# booster.net
KiCad netlist of a schematic drawn in Altium Designer
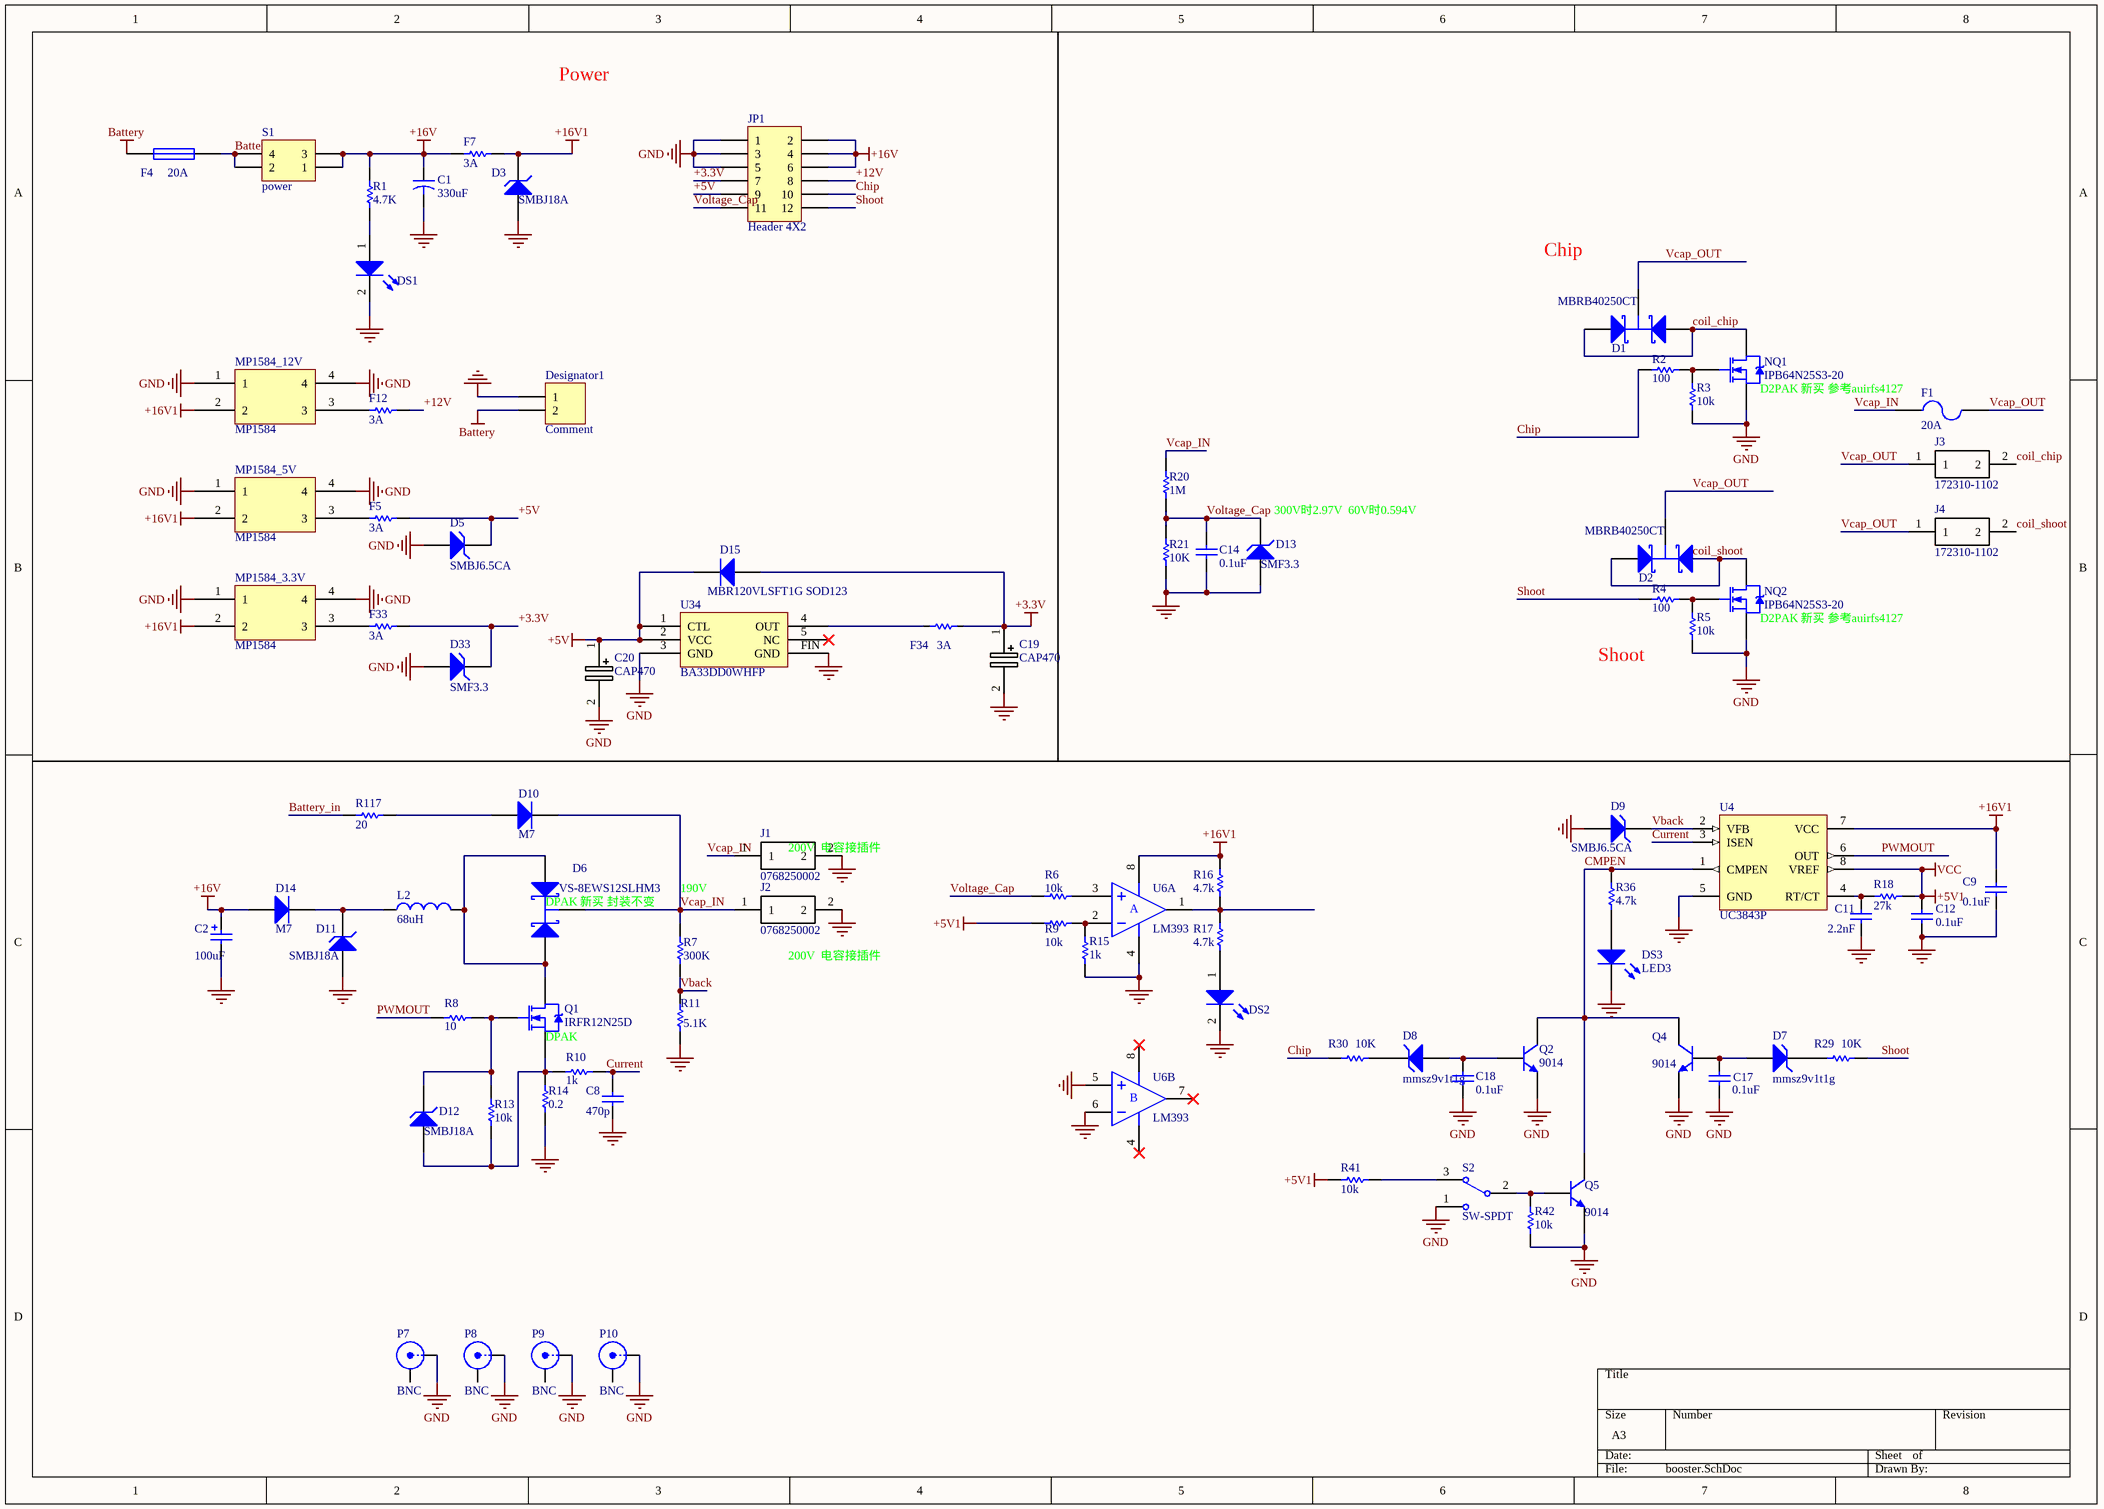
[diagram p0: booster.SchDoc]

(export (version "E")
  (design (tool "Eeschema 10.0.6"))
  (components
    (comp (ref "C1")
      (value "330uF")
      (footprint "470uF")
      (description "Capacitor")
      (fields (field (name "PUBLISHER") "Altium Limited"))
      (libsource (lib "Miscellaneous Devices") (part "Cap2"))
    )
    (comp (ref "C2")
      (value "100uF")
      (footprint "100uF")
      (description "Polarized Capacitor (Radial)")
      (fields
        (field (name "MANUFACTURER") "Generic Components")
        (field (name "Comment") "100uf")
        (field (name "PUBLISHER") "Altium Hobart Technology Centre")
      )
      (libsource (lib "Miscellaneous Devices") (part "Cap Pol1"))
    )
    (comp (ref "C8")
      (value "470p")
      (footprint "0805C")
      (description "Capacitor")
      (fields
        (field (name "MANUFACTURER") "Generic Components")
        (field (name "PUBLISHER") "Altium Hobart Technology Centre")
      )
      (libsource (lib "Miscellaneous Devices") (part "Cap"))
    )
    (comp (ref "C9")
      (value "0.1uF")
      (footprint "0805C")
      (description "Capacitor")
      (fields (field (name "PUBLISHER") "Altium Limited"))
      (libsource (lib "Miscellaneous Devices") (part "Cap"))
    )
    (comp (ref "C11")
      (value "2.2nF")
      (footprint "0805C")
      (description "Capacitor")
      (fields
        (field (name "MANUFACTURER") "Generic Components")
        (field (name "Comment") "2.2nf")
        (field (name "PUBLISHER") "Altium Hobart Technology Centre")
      )
      (libsource (lib "Miscellaneous Devices") (part "Cap"))
    )
    (comp (ref "C12")
      (value "0.1uF")
      (footprint "0805C")
      (description "Capacitor")
      (fields
        (field (name "MANUFACTURER") "Generic Components")
        (field (name "PUBLISHER") "Altium Hobart Technology Centre")
      )
      (libsource (lib "Miscellaneous Devices") (part "Cap"))
    )
    (comp (ref "C14")
      (value "0.1uF")
      (footprint "0805C")
      (description "Capacitor")
      (fields (field (name "PUBLISHER") "Altium Limited"))
      (libsource (lib "Miscellaneous Devices") (part "Cap"))
    )
    (comp (ref "C17")
      (value "0.1uF")
      (footprint "0805c")
      (description "Capacitor")
      (fields (field (name "PUBLISHER") "Altium Limited"))
      (libsource (lib "Miscellaneous Devices") (part "Cap"))
    )
    (comp (ref "C18")
      (value "0.1uF")
      (footprint "0805c")
      (description "Capacitor")
      (fields (field (name "PUBLISHER") "Altium Limited"))
      (libsource (lib "Miscellaneous Devices") (part "Cap"))
    )
    (comp (ref "C19")
      (value "CAP470")
      (footprint "Main_Board:CAPPM7360X200N")
      (description "470uF电容贴片")
      (fields
        (field (name "MANUFACTURER_PART_NUMBER") "T523H477M016APE0707280")
        (field (name "MOUSER PART NUMBER") "80-T523H477M16P070LR")
      )
      (libsource (lib "Main_Board") (part "T523H477M016APE0707280"))
    )
    (comp (ref "C20")
      (value "CAP470")
      (footprint "Main_Board:CAPPM7360X200N")
      (description "470uF电容贴片")
      (fields
        (field (name "MANUFACTURER_PART_NUMBER") "T523H477M016APE0707280")
        (field (name "MOUSER PART NUMBER") "80-T523H477M16P070LR")
      )
      (libsource (lib "Main_Board") (part "T523H477M016APE0707280"))
    )
    (comp (ref "D1")
      (value "MBRB40250CT")
      (footprint "D2PAK")
      (description "Schottky Rectifier")
      (fields
        (field (name "MANUFACTURER") "International Rectifier")
        (field (name "PUBLISHER") "Altium Hobart Technology Centre")
      )
      (libsource (lib "IR Discrete Diode") (part "MBRB1545CT"))
    )
    (comp (ref "D2")
      (value "MBRB40250CT")
      (footprint "D2PAK")
      (description "Schottky Rectifier")
      (fields
        (field (name "MANUFACTURER") "International Rectifier")
        (field (name "PUBLISHER") "Altium Hobart Technology Centre")
      )
      (libsource (lib "IR Discrete Diode") (part "MBRB1545CT"))
    )
    (comp (ref "D3")
      (value "SMBJ18A")
      (footprint "booster:SMBJ6.5")
      (description "Zener Diode")
      (fields (field (name "PUBLISHER") "Altium Limited"))
      (libsource (lib "Miscellaneous Devices") (part "D Zener"))
    )
    (comp (ref "D5")
      (value "SMBJ6.5CA")
      (footprint "SMBJ6.5")
      (description "Zener Diode")
      (fields (field (name "PUBLISHER") "Altium Limited"))
      (libsource (lib "Miscellaneous Devices") (part "D Zener"))
    )
    (comp (ref "D6")
      (value "VS-8EWS12SLHM3")
      (footprint "DPAK")
      (description "Schottky Rectifier")
      (fields
        (field (name "MANUFACTURER") "International Rectifier")
        (field (name "PUBLISHER") "Altium Hobart Technology Centre")
      )
      (libsource (lib "IR Discrete Diode") (part "MBRB1545CT"))
    )
    (comp (ref "D7")
      (value "mmsz9v1t1g")
      (footprint "sod-123")
      (description "Zener Diode")
      (fields (field (name "PUBLISHER") "Altium Limited"))
      (libsource (lib "Miscellaneous Devices") (part "D Zener"))
    )
    (comp (ref "D8")
      (value "mmsz9v1t1g")
      (footprint "sod-123")
      (description "Zener Diode")
      (fields (field (name "PUBLISHER") "Altium Limited"))
      (libsource (lib "Miscellaneous Devices") (part "D Zener"))
    )
    (comp (ref "D9")
      (value "SMBJ6.5CA")
      (footprint "SMBJ6.5")
      (description "Zener Diode")
      (fields (field (name "PUBLISHER") "Altium Limited"))
      (libsource (lib "Miscellaneous Devices") (part "D Zener"))
    )
    (comp (ref "D10")
      (value "M7")
      (footprint "booster:SMA")
      (description "Default Diode")
      (fields
        (field (name "MANUFACTURER") "Generic Components")
        (field (name "PUBLISHER") "Altium Hobart Technology Centre")
      )
      (libsource (lib "Miscellaneous Devices") (part "Diode"))
    )
    (comp (ref "D11")
      (value "SMBJ18A")
      (footprint "booster:SMBJ6.5")
      (description "Zener Diode")
      (fields (field (name "PUBLISHER") "Altium Limited"))
      (libsource (lib "Miscellaneous Devices") (part "D Zener"))
    )
    (comp (ref "D12")
      (value "SMBJ18A")
      (footprint "SMBJ6.5")
      (description "Zener Diode")
      (fields (field (name "PUBLISHER") "Altium Limited"))
      (libsource (lib "Miscellaneous Devices") (part "D Zener"))
    )
    (comp (ref "D13")
      (value "SMF3.3")
      (footprint "SMF33")
      (description "Zener Diode")
      (fields (field (name "PUBLISHER") "Altium Limited"))
      (libsource (lib "Miscellaneous Devices") (part "D Zener"))
    )
    (comp (ref "D14")
      (value "M7")
      (footprint "booster:SMA")
      (description "Default Diode")
      (fields
        (field (name "MANUFACTURER") "Generic Components")
        (field (name "PUBLISHER") "Altium Hobart Technology Centre")
      )
      (libsource (lib "Miscellaneous Devices") (part "Diode"))
    )
    (comp (ref "D15")
      (value "MBR120VLSFT1G SOD123")
      (footprint "Main_Board:sod123")
      (description "Default Diode")
      (fields
        (field (name "MANUFACTURER") "Generic Components")
        (field (name "PUBLISHER") "Altium Hobart Technology Centre")
      )
      (libsource (lib "Miscellaneous Devices") (part "Diode"))
    )
    (comp (ref "D33")
      (value "SMF3.3")
      (footprint "SMF33")
      (description "Zener Diode")
      (fields (field (name "PUBLISHER") "Altium Limited"))
      (libsource (lib "Miscellaneous Devices") (part "D Zener"))
    )
    (comp (ref "Designator1")
      (value "Comment")
      (footprint "XT60PW")
      (description "Header, 2-Pin")
      (fields (field (name "PUBLISHER") "Altium Limited"))
      (libsource (lib "Miscellaneous Connectors") (part "Header 2"))
    )
    (comp (ref "DS1")
      (value "LED2")
      (footprint "0805A")
      (description "Typical RED, GREEN, YELLOW, AMBER GaAs LED")
      (fields
        (field (name "MANUFACTURER") "Generic Components")
        (field (name "PUBLISHER") "Altium Hobart Technology Centre")
      )
      (libsource (lib "Miscellaneous Devices") (part "LED2"))
    )
    (comp (ref "DS2")
      (value "LED2")
      (footprint "0805A")
      (description "Typical RED, GREEN, YELLOW, AMBER GaAs LED")
      (fields
        (field (name "MANUFACTURER") "Generic Components")
        (field (name "PUBLISHER") "Altium Hobart Technology Centre")
      )
      (libsource (lib "Miscellaneous Devices") (part "LED2"))
    )
    (comp (ref "DS3")
      (value "LED3")
      (footprint "booster:0805A")
      (description "Typical RED, GREEN, YELLOW, AMBER GaAs LED")
      (fields (field (name "PUBLISHER") "Altium Limited"))
      (libsource (lib "") (part "LED2_1"))
    )
    (comp (ref "F1")
      (value "20A")
      (footprint "20A")
      (fields (field (name "PUBLISHER") "Altium Limited"))
      (libsource (lib "Miscellaneous Devices") (part "Fuse 2"))
    )
    (comp (ref "F4")
      (value "20A")
      (footprint "20A")
      (description "Fuse")
      (fields (field (name "PUBLISHER") "Altium Limited"))
      (libsource (lib "Miscellaneous Devices") (part "Fuse 1"))
    )
    (comp (ref "F5")
      (value "3A")
      (footprint "2512r")
      (description "Resistor")
      (fields
        (field (name "MANUFACTURER") "Generic Components")
        (field (name "PUBLISHER") "Altium Hobart Technology Centre")
      )
      (libsource (lib "Miscellaneous Devices") (part "Res1"))
    )
    (comp (ref "F7")
      (value "3A")
      (footprint "2512r")
      (description "Resistor")
      (fields
        (field (name "MANUFACTURER") "Generic Components")
        (field (name "PUBLISHER") "Altium Hobart Technology Centre")
      )
      (libsource (lib "Miscellaneous Devices") (part "Res1"))
    )
    (comp (ref "F12")
      (value "3A")
      (footprint "2512r")
      (description "Resistor")
      (fields
        (field (name "MANUFACTURER") "Generic Components")
        (field (name "PUBLISHER") "Altium Hobart Technology Centre")
      )
      (libsource (lib "Miscellaneous Devices") (part "Res1"))
    )
    (comp (ref "F33")
      (value "3A")
      (footprint "2512r")
      (description "Resistor")
      (fields
        (field (name "MANUFACTURER") "Generic Components")
        (field (name "PUBLISHER") "Altium Hobart Technology Centre")
      )
      (libsource (lib "Miscellaneous Devices") (part "Res1"))
    )
    (comp (ref "F34")
      (value "3A")
      (footprint "2512r")
      (description "Resistor")
      (fields (field (name "PUBLISHER") "Altium Limited"))
      (libsource (lib "") (part "Res1_1"))
    )
    (comp (ref "J1")
      (value "0768250002")
      (footprint "booster:0768250002_version2")
      (description "Connector")
      (libsource (lib "booster") (part "0768250002"))
    )
    (comp (ref "J2")
      (value "0768250002")
      (footprint "booster:0768250002_version2")
      (description "Connector")
      (libsource (lib "booster") (part "0768250002"))
    )
    (comp (ref "J3")
      (value "172310-1102")
      (footprint "booster:172310-1102_VERSION2")
      (description "Connector")
      (fields (field (name "MOUSER PART NUMBER") "538-172310-1102") (field (name "RS PART NUMBER") "8951880"))
      (libsource (lib "booster") (part "172310-1102"))
    )
    (comp (ref "J4")
      (value "172310-1102")
      (footprint "booster:172310-1102_VERSION2")
      (description "Connector")
      (fields (field (name "MOUSER PART NUMBER") "538-172310-1102") (field (name "RS PART NUMBER") "8951880"))
      (libsource (lib "booster") (part "172310-1102"))
    )
    (comp (ref "JP1")
      (value "Header 4X2")
      (footprint "2*6_2.5mm")
      (description "Header, 4-Pin, Dual row")
      (fields (field (name "PUBLISHER") "Altium Limited"))
      (libsource (lib "booster") (part "Header 6X2"))
    )
    (comp (ref "L2")
      (value "68uH")
      (footprint "INDPM120120X1020N")
      (description "Inductor")
      (fields (field (name "PUBLISHER") "Altium Limited"))
      (libsource (lib "Miscellaneous Devices") (part "Inductor"))
    )
    (comp (ref "MP1584_3.3V") (value "MP1584") (footprint "1584") (libsource (lib "booster") (part "MP1584")))
    (comp (ref "MP1584_5V") (value "MP1584") (footprint "1584") (libsource (lib "booster") (part "MP1584")))
    (comp (ref "MP1584_12V") (value "MP1584") (footprint "1584") (libsource (lib "booster") (part "MP1584")))
    (comp (ref "NQ1")
      (value "IPB64N25S3-20")
      (footprint "D2PAK")
      (description "HEXFET Power MOSFET")
      (fields
        (field (name "MANUFACTURER") "International Rectifier")
        (field (name "PUBLISHER") "Altium Hobart Technology Centre")
      )
      (libsource (lib "IR Discrete MOSFET") (part "IRFP460"))
    )
    (comp (ref "NQ2")
      (value "IPB64N25S3-20")
      (footprint "D2PAK")
      (description "HEXFET Power MOSFET")
      (fields
        (field (name "MANUFACTURER") "International Rectifier")
        (field (name "PUBLISHER") "Altium Hobart Technology Centre")
      )
      (libsource (lib "IR Discrete MOSFET") (part "IRFP460"))
    )
    (comp (ref "P7")
      (value "BNC")
      (footprint "hole")
      (description "BNC Elbow Connector")
      (fields (field (name "PUBLISHER") "Altium Limited"))
      (libsource (lib "Miscellaneous Connectors") (part "BNC"))
    )
    (comp (ref "P8")
      (value "BNC")
      (footprint "hole")
      (description "BNC Elbow Connector")
      (fields (field (name "PUBLISHER") "Altium Limited"))
      (libsource (lib "Miscellaneous Connectors") (part "BNC"))
    )
    (comp (ref "P9")
      (value "BNC")
      (footprint "hole")
      (description "BNC Elbow Connector")
      (fields (field (name "PUBLISHER") "Altium Limited"))
      (libsource (lib "Miscellaneous Connectors") (part "BNC"))
    )
    (comp (ref "P10")
      (value "BNC")
      (footprint "hole")
      (description "BNC Elbow Connector")
      (fields (field (name "PUBLISHER") "Altium Limited"))
      (libsource (lib "Miscellaneous Connectors") (part "BNC"))
    )
    (comp (ref "Q1")
      (value "IRFR12N25D")
      (footprint "DPAK")
      (description "N-Channel Power MOSFET")
      (fields (field (name "PUBLISHER") "Altium Limited"))
      (libsource (lib "Miscellaneous Devices") (part "NMOS-2"))
    )
    (comp (ref "Q2")
      (value "9014")
      (footprint "元器件:SOT23A")
      (description "NPN General Purpose Amplifier")
      (fields
        (field (name "MANUFACTURER") "Fairchild Semiconductor")
        (field (name "PUBLISHER") "Altium Hobart Technology Centre")
      )
      (libsource (lib "FSC Discrete BJT") (part "BC817-40"))
    )
    (comp (ref "Q4")
      (value "9014")
      (footprint "sot23a")
      (description "NPN General Purpose Amplifier")
      (fields
        (field (name "MANUFACTURER") "Fairchild Semiconductor")
        (field (name "PUBLISHER") "Altium Hobart Technology Centre")
      )
      (libsource (lib "FSC Discrete BJT") (part "BC817-40"))
    )
    (comp (ref "Q5")
      (value "9014")
      (footprint "SOT23a")
      (description "NPN General Purpose Amplifier")
      (fields
        (field (name "MANUFACTURER") "Fairchild Semiconductor")
        (field (name "PUBLISHER") "Altium Hobart Technology Centre")
      )
      (libsource (lib "FSC Discrete BJT") (part "BC817-40"))
    )
    (comp (ref "R1")
      (value "4.7K")
      (footprint "0805R")
      (description "Resistor")
      (fields
        (field (name "MANUFACTURER") "Generic Components")
        (field (name "Comment") "4.7k")
        (field (name "PUBLISHER") "Altium Hobart Technology Centre")
      )
      (libsource (lib "Miscellaneous Devices") (part "Res1"))
    )
    (comp (ref "R2")
      (value "100")
      (footprint "0805r")
      (description "Semiconductor Resistor")
      (fields
        (field (name "MANUFACTURER") "Generic Components")
        (field (name "PUBLISHER") "Altium Hobart Technology Centre")
      )
      (libsource (lib "Miscellaneous Devices") (part "Res Semi"))
    )
    (comp (ref "R3")
      (value "10k")
      (footprint "0805R")
      (description "Semiconductor Resistor")
      (fields
        (field (name "MANUFACTURER") "Generic Components")
        (field (name "PUBLISHER") "Altium Hobart Technology Centre")
      )
      (libsource (lib "Miscellaneous Devices") (part "Res Semi"))
    )
    (comp (ref "R4")
      (value "100")
      (footprint "0805r")
      (description "Semiconductor Resistor")
      (fields
        (field (name "MANUFACTURER") "Generic Components")
        (field (name "PUBLISHER") "Altium Hobart Technology Centre")
      )
      (libsource (lib "Miscellaneous Devices") (part "Res Semi"))
    )
    (comp (ref "R5")
      (value "10k")
      (footprint "0805R")
      (description "Semiconductor Resistor")
      (fields
        (field (name "MANUFACTURER") "Generic Components")
        (field (name "PUBLISHER") "Altium Hobart Technology Centre")
      )
      (libsource (lib "Miscellaneous Devices") (part "Res Semi"))
    )
    (comp (ref "R6")
      (value "10k")
      (footprint "0805R")
      (description "Resistor")
      (fields
        (field (name "MANUFACTURER") "Generic Components")
        (field (name "PUBLISHER") "Altium Hobart Technology Centre")
      )
      (libsource (lib "HAIBAO_MEGAV1.0_1") (part "Res1"))
    )
    (comp (ref "R7")
      (value "300K")
      (footprint "0805R")
      (description "Resistor")
      (fields
        (field (name "MANUFACTURER") "Generic Components")
        (field (name "Comment") "390K")
        (field (name "PUBLISHER") "Altium Hobart Technology Centre")
      )
      (libsource (lib "Miscellaneous Devices") (part "Res1"))
    )
    (comp (ref "R8")
      (value "10")
      (footprint "0805R")
      (description "Resistor")
      (fields
        (field (name "MANUFACTURER") "Generic Components")
        (field (name "PUBLISHER") "Altium Hobart Technology Centre")
      )
      (libsource (lib "Miscellaneous Devices") (part "Res1"))
    )
    (comp (ref "R9")
      (value "10k")
      (footprint "0805R")
      (description "Resistor")
      (fields
        (field (name "MANUFACTURER") "Generic Components")
        (field (name "PUBLISHER") "Altium Hobart Technology Centre")
      )
      (libsource (lib "HAIBAO_MEGAV1.0_1") (part "Res1"))
    )
    (comp (ref "R10")
      (value "1k")
      (footprint "0805R")
      (description "Resistor")
      (fields
        (field (name "MANUFACTURER") "Generic Components")
        (field (name "PUBLISHER") "Altium Hobart Technology Centre")
      )
      (libsource (lib "Miscellaneous Devices") (part "Res1"))
    )
    (comp (ref "R11")
      (value "5.1K")
      (footprint "0805R")
      (description "Resistor")
      (fields
        (field (name "MANUFACTURER") "Generic Components")
        (field (name "Comment") "3.3K")
        (field (name "PUBLISHER") "Altium Hobart Technology Centre")
      )
      (libsource (lib "Miscellaneous Devices") (part "Res1"))
    )
    (comp (ref "R13")
      (value "10k")
      (footprint "0805R")
      (description "Resistor")
      (fields
        (field (name "MANUFACTURER") "Generic Components")
        (field (name "PUBLISHER") "Altium Hobart Technology Centre")
      )
      (libsource (lib "Miscellaneous Devices") (part "Res1"))
    )
    (comp (ref "R14")
      (value "0.2")
      (footprint "0.2_4527R")
      (description "Resistor")
      (fields
        (field (name "MANUFACTURER") "Generic Components")
        (field (name "PUBLISHER") "Altium Hobart Technology Centre")
      )
      (libsource (lib "Miscellaneous Devices") (part "Res1"))
    )
    (comp (ref "R15")
      (value "1k")
      (footprint "0805R")
      (description "Resistor")
      (fields
        (field (name "MANUFACTURER") "Generic Components")
        (field (name "PUBLISHER") "Altium Hobart Technology Centre")
      )
      (libsource (lib "HAIBAO_MEGAV1.0_1") (part "Res1"))
    )
    (comp (ref "R16")
      (value "4.7k")
      (footprint "0805R")
      (description "Resistor")
      (fields
        (field (name "MANUFACTURER") "Generic Components")
        (field (name "PUBLISHER") "Altium Hobart Technology Centre")
      )
      (libsource (lib "HAIBAO_MEGAV1.0_1") (part "Res1"))
    )
    (comp (ref "R17")
      (value "4.7k")
      (footprint "0805R")
      (description "Resistor")
      (fields
        (field (name "MANUFACTURER") "Generic Components")
        (field (name "PUBLISHER") "Altium Hobart Technology Centre")
      )
      (libsource (lib "HAIBAO_MEGAV1.0_1") (part "Res1"))
    )
    (comp (ref "R18")
      (value "27k")
      (footprint "0805R")
      (description "Resistor")
      (fields
        (field (name "MANUFACTURER") "Generic Components")
        (field (name "PUBLISHER") "Altium Hobart Technology Centre")
      )
      (libsource (lib "Miscellaneous Devices") (part "Res1"))
    )
    (comp (ref "R20")
      (value "1M")
      (footprint "0805R")
      (description "Resistor")
      (fields
        (field (name "MANUFACTURER") "Generic Components")
        (field (name "Comment") "200k")
        (field (name "PUBLISHER") "Altium Hobart Technology Centre")
      )
      (libsource (lib "Miscellaneous Devices") (part "Res1"))
    )
    (comp (ref "R21")
      (value "10K")
      (footprint "0805R")
      (description "Resistor")
      (fields
        (field (name "MANUFACTURER") "Generic Components")
        (field (name "Comment") "3.9k")
        (field (name "PUBLISHER") "Altium Hobart Technology Centre")
      )
      (libsource (lib "Miscellaneous Devices") (part "Res1"))
    )
    (comp (ref "R29")
      (value "10K")
      (footprint "0805r")
      (description "Resistor")
      (fields
        (field (name "MANUFACTURER") "Generic Components")
        (field (name "Comment") "10k")
        (field (name "PUBLISHER") "Altium Hobart Technology Centre")
      )
      (libsource (lib "Miscellaneous Devices") (part "Res1"))
    )
    (comp (ref "R30")
      (value "10K")
      (footprint "0805r")
      (description "Resistor")
      (fields
        (field (name "MANUFACTURER") "Generic Components")
        (field (name "Comment") "10k")
        (field (name "PUBLISHER") "Altium Hobart Technology Centre")
      )
      (libsource (lib "Miscellaneous Devices") (part "Res1"))
    )
    (comp (ref "R36")
      (value "4.7k")
      (footprint "0805r")
      (description "Resistor")
      (fields
        (field (name "MANUFACTURER") "Generic Components")
        (field (name "PUBLISHER") "Altium Hobart Technology Centre")
      )
      (libsource (lib "Miscellaneous Devices") (part "Res1"))
    )
    (comp (ref "R41")
      (value "10k")
      (footprint "0805r")
      (description "Resistor")
      (fields
        (field (name "MANUFACTURER") "Generic Components")
        (field (name "PUBLISHER") "Altium Hobart Technology Centre")
      )
      (libsource (lib "Miscellaneous Devices") (part "Res1"))
    )
    (comp (ref "R42")
      (value "10k")
      (footprint "0805r")
      (description "Resistor")
      (fields
        (field (name "MANUFACTURER") "Generic Components")
        (field (name "PUBLISHER") "Altium Hobart Technology Centre")
      )
      (libsource (lib "Miscellaneous Devices") (part "Res1"))
    )
    (comp (ref "R117")
      (value "20")
      (footprint "20_2512r")
      (description "Resistor")
      (fields
        (field (name "MANUFACTURER") "Generic Components")
        (field (name "PUBLISHER") "Altium Hobart Technology Centre")
      )
      (libsource (lib "Miscellaneous Devices") (part "Res1"))
    )
    (comp (ref "S1")
      (value "power")
      (footprint "Rocker_Switch")
      (description "Header, 2-Pin, Dual row")
      (fields (field (name "PUBLISHER") "Altium Limited"))
      (libsource (lib "Miscellaneous Connectors") (part "Header 2X2"))
    )
    (comp (ref "S2")
      (value "SW-SPDT")
      (footprint "SMALL_switch")
      (description "SPDT Subminiature Toggle Switch, Right Angle Mounting, Vertical Actuation")
      (fields (field (name "PUBLISHER") "Altium Limited"))
      (libsource (lib "Miscellaneous Devices") (part "SW-SPDT"))
    )
    (comp (ref "U4")
      (value "UC3843P")
      (footprint "SO-G8")
      (description "Current-Mode PWM Controller")
      (fields (field (name "PUBLISHER") "Altium Limited"))
      (libsource (lib "TI Power Mgt DC-DC Converter") (part "UC3843P"))
    )
    (comp (ref "U6")
      (value "LM393")
      (footprint "LM393_SO-G8")
      (libsource (lib "HAIBAO_MEGAV1.0_1") (part "LM393"))
    )
    (comp (ref "U34")
      (value "BA33DD0WHFP")
      (footprint "Main_Board:HRP5_16TO5")
      (libsource (lib "Main_Board") (part "HRP5-16TO5"))
    )
  )
  (nets
    (net (code "1") (name "+3.3V") (class "Default")
      (node (ref "C19") (pin "1") (pinfunction "+_1") (pintype "passive"))
      (node (ref "D15") (pin "1") (pinfunction "A_1") (pintype "passive"))
      (node (ref "D33") (pin "2") (pinfunction "K_2") (pintype "passive"))
      (node (ref "F33") (pin "1") (pinfunction "1_1") (pintype "passive"))
      (node (ref "F34") (pin "2") (pinfunction "2_2") (pintype "passive"))
      (node (ref "JP1") (pin "7") (pinfunction "7_7") (pintype "passive"))
    )
    (net (code "2") (name "+5V") (class "Default")
      (node (ref "C20") (pin "1") (pinfunction "+_1") (pintype "passive"))
      (node (ref "D15") (pin "2") (pinfunction "K_2") (pintype "passive"))
      (node (ref "D5") (pin "2") (pinfunction "K_2") (pintype "passive"))
      (node (ref "F5") (pin "1") (pinfunction "1_1") (pintype "passive"))
      (node (ref "JP1") (pin "9") (pinfunction "9_9") (pintype "passive"))
      (node (ref "U34") (pin "1") (pinfunction "CTL_1") (pintype "passive"))
      (node (ref "U34") (pin "2") (pinfunction "VCC_2") (pintype "passive"))
    )
    (net (code "3") (name "+5V1") (class "Default")
      (node (ref "C12") (pin "1") (pinfunction "1_1") (pintype "passive"))
      (node (ref "R18") (pin "2") (pinfunction "2_2") (pintype "passive"))
      (node (ref "R41") (pin "2") (pinfunction "2_2") (pintype "passive"))
      (node (ref "R9") (pin "2") (pinfunction "2_2") (pintype "passive"))
      (node (ref "U4") (pin "8") (pinfunction "VREF_8") (pintype "output"))
    )
    (net (code "4") (name "+16V") (class "Default")
      (node (ref "C1") (pin "1") (pinfunction "1_1") (pintype "passive"))
      (node (ref "C2") (pin "1") (pinfunction "1_1") (pintype "passive"))
      (node (ref "D14") (pin "1") (pinfunction "A_1") (pintype "passive"))
      (node (ref "F7") (pin "2") (pinfunction "2_2") (pintype "passive"))
      (node (ref "JP1") (pin "2") (pinfunction "2_2") (pintype "passive"))
      (node (ref "JP1") (pin "4") (pinfunction "4_4") (pintype "passive"))
      (node (ref "JP1") (pin "6") (pinfunction "6_6") (pintype "passive"))
      (node (ref "R1") (pin "2") (pinfunction "2_2") (pintype "passive"))
      (node (ref "S1") (pin "1") (pinfunction "1_1") (pintype "passive"))
      (node (ref "S1") (pin "3") (pinfunction "3_3") (pintype "passive"))
    )
    (net (code "5") (name "+16V1") (class "Default")
      (node (ref "C9") (pin "2") (pinfunction "2_2") (pintype "passive"))
      (node (ref "D3") (pin "2") (pinfunction "K_2") (pintype "passive"))
      (node (ref "F7") (pin "1") (pinfunction "1_1") (pintype "passive"))
      (node (ref "MP1584_12V") (pin "2") (pinfunction "2_2") (pintype "passive"))
      (node (ref "MP1584_3.3V") (pin "2") (pinfunction "2_2") (pintype "passive"))
      (node (ref "MP1584_5V") (pin "2") (pinfunction "2_2") (pintype "passive"))
      (node (ref "R16") (pin "2") (pinfunction "2_2") (pintype "passive"))
      (node (ref "U4") (pin "7") (pinfunction "VCC_7") (pintype "power_in"))
      (node (ref "U6") (pin "8") (pinfunction "V+_8") (pintype "power_in"))
    )
    (net (code "6") (name "/+12V") (class "Default")
      (node (ref "F12") (pin "1") (pinfunction "1_1") (pintype "passive"))
      (node (ref "JP1") (pin "8") (pinfunction "8_8") (pintype "passive"))
    )
    (net (code "7") (name "/Battery_in") (class "Default")
      (node (ref "F4") (pin "1") (pinfunction "1_1") (pintype "passive"))
      (node (ref "R117") (pin "2") (pinfunction "2_2") (pintype "passive"))
      (node (ref "S1") (pin "2") (pinfunction "2_2") (pintype "passive"))
      (node (ref "S1") (pin "4") (pinfunction "4_4") (pintype "passive"))
    )
    (net (code "8") (name "/CMPEN") (class "Default")
      (node (ref "Q2") (pin "3") (pinfunction "C_3") (pintype "passive"))
      (node (ref "Q4") (pin "3") (pinfunction "C_3") (pintype "passive"))
      (node (ref "Q5") (pin "3") (pinfunction "C_3") (pintype "passive"))
      (node (ref "R36") (pin "2") (pinfunction "2_2") (pintype "passive"))
      (node (ref "U4") (pin "1") (pinfunction "CMPEN_1") (pintype "output"))
    )
    (net (code "9") (name "/Chip") (class "Default")
      (node (ref "JP1") (pin "10") (pinfunction "10_10") (pintype "passive"))
      (node (ref "R2") (pin "1") (pinfunction "1_1") (pintype "passive"))
      (node (ref "R30") (pin "1") (pinfunction "1_1") (pintype "passive"))
    )
    (net (code "10") (name "/Current") (class "Default")
      (node (ref "C8") (pin "1") (pinfunction "1_1") (pintype "passive"))
      (node (ref "R10") (pin "2") (pinfunction "2_2") (pintype "passive"))
      (node (ref "U4") (pin "3") (pinfunction "ISEN_3") (pintype "input"))
    )
    (net (code "11") (name "/PWMOUT") (class "Default")
      (node (ref "R8") (pin "1") (pinfunction "1_1") (pintype "passive"))
      (node (ref "U4") (pin "6") (pinfunction "OUT_6") (pintype "output"))
    )
    (net (code "12") (name "/Shoot") (class "Default")
      (node (ref "JP1") (pin "12") (pinfunction "12_12") (pintype "passive"))
      (node (ref "R29") (pin "2") (pinfunction "2_2") (pintype "passive"))
      (node (ref "R4") (pin "1") (pinfunction "1_1") (pintype "passive"))
    )
    (net (code "13") (name "/Vback") (class "Default")
      (node (ref "D9") (pin "2") (pinfunction "K_2") (pintype "passive"))
      (node (ref "R11") (pin "2") (pinfunction "2_2") (pintype "passive"))
      (node (ref "R7") (pin "1") (pinfunction "1_1") (pintype "passive"))
      (node (ref "U4") (pin "2") (pinfunction "VFB_2") (pintype "input"))
    )
    (net (code "14") (name "/Vcap_IN") (class "Default")
      (node (ref "D10") (pin "2") (pinfunction "K_2") (pintype "passive"))
      (node (ref "D6") (pin "2") (pinfunction "K_2") (pintype "passive"))
      (node (ref "F1") (pin "1") (pinfunction "1_1") (pintype "passive"))
      (node (ref "J1") (pin "1") (pinfunction "1_1") (pintype "passive"))
      (node (ref "J2") (pin "1") (pinfunction "1_1") (pintype "passive"))
      (node (ref "R20") (pin "2") (pinfunction "2_2") (pintype "passive"))
      (node (ref "R7") (pin "2") (pinfunction "2_2") (pintype "passive"))
    )
    (net (code "15") (name "/Vcap_OUT") (class "Default")
      (node (ref "D1") (pin "2") (pinfunction "K_2") (pintype "passive"))
      (node (ref "D2") (pin "2") (pinfunction "K_2") (pintype "passive"))
      (node (ref "F1") (pin "2") (pinfunction "2_2") (pintype "passive"))
      (node (ref "J3") (pin "1") (pinfunction "1_1") (pintype "passive"))
      (node (ref "J4") (pin "1") (pinfunction "1_1") (pintype "passive"))
    )
    (net (code "16") (name "/Voltage_Cap") (class "Default")
      (node (ref "C14") (pin "2") (pinfunction "2_2") (pintype "passive"))
      (node (ref "D13") (pin "2") (pinfunction "K_2") (pintype "passive"))
      (node (ref "JP1") (pin "11") (pinfunction "11_11") (pintype "passive"))
      (node (ref "R20") (pin "1") (pinfunction "1_1") (pintype "passive"))
      (node (ref "R21") (pin "2") (pinfunction "2_2") (pintype "passive"))
      (node (ref "R6") (pin "2") (pinfunction "2_2") (pintype "passive"))
    )
    (net (code "17") (name "/coil_chip") (class "Default")
      (node (ref "D1") (pin "1") (pinfunction "A1_1") (pintype "passive"))
      (node (ref "D1") (pin "3") (pinfunction "A2_3") (pintype "passive"))
      (node (ref "J3") (pin "2") (pinfunction "2_2") (pintype "passive"))
      (node (ref "NQ1") (pin "2") (pinfunction "D_2") (pintype "passive"))
    )
    (net (code "18") (name "/coil_shoot") (class "Default")
      (node (ref "D2") (pin "1") (pinfunction "A1_1") (pintype "passive"))
      (node (ref "D2") (pin "3") (pinfunction "A2_3") (pintype "passive"))
      (node (ref "J4") (pin "2") (pinfunction "2_2") (pintype "passive"))
      (node (ref "NQ2") (pin "2") (pinfunction "D_2") (pintype "passive"))
    )
    (net (code "19") (name "Battery") (class "Default")
      (node (ref "Designator1") (pin "2") (pinfunction "2_2") (pintype "passive"))
      (node (ref "F4") (pin "2") (pinfunction "2_2") (pintype "passive"))
    )
    (net (code "20") (name "GND") (class "Default")
      (node (ref "C1") (pin "2") (pinfunction "2_2") (pintype "passive"))
      (node (ref "C11") (pin "2") (pinfunction "2_2") (pintype "passive"))
      (node (ref "C12") (pin "2") (pinfunction "2_2") (pintype "passive"))
      (node (ref "C14") (pin "1") (pinfunction "1_1") (pintype "passive"))
      (node (ref "C17") (pin "1") (pinfunction "1_1") (pintype "passive"))
      (node (ref "C18") (pin "1") (pinfunction "1_1") (pintype "passive"))
      (node (ref "C19") (pin "2") (pinfunction "-_2") (pintype "passive"))
      (node (ref "C2") (pin "2") (pinfunction "2_2") (pintype "passive"))
      (node (ref "C20") (pin "2") (pinfunction "-_2") (pintype "passive"))
      (node (ref "C8") (pin "2") (pinfunction "2_2") (pintype "passive"))
      (node (ref "C9") (pin "1") (pinfunction "1_1") (pintype "passive"))
      (node (ref "D11") (pin "1") (pinfunction "A_1") (pintype "passive"))
      (node (ref "D13") (pin "1") (pinfunction "A_1") (pintype "passive"))
      (node (ref "D3") (pin "1") (pinfunction "A_1") (pintype "passive"))
      (node (ref "D33") (pin "1") (pinfunction "A_1") (pintype "passive"))
      (node (ref "D5") (pin "1") (pinfunction "A_1") (pintype "passive"))
      (node (ref "D9") (pin "1") (pinfunction "A_1") (pintype "passive"))
      (node (ref "DS1") (pin "2") (pinfunction "K_2") (pintype "passive"))
      (node (ref "DS2") (pin "2") (pinfunction "K_2") (pintype "passive"))
      (node (ref "DS3") (pin "2") (pinfunction "K_2") (pintype "passive"))
      (node (ref "Designator1") (pin "1") (pinfunction "1_1") (pintype "passive"))
      (node (ref "J1") (pin "2") (pinfunction "2_2") (pintype "passive"))
      (node (ref "J2") (pin "2") (pinfunction "2_2") (pintype "passive"))
      (node (ref "JP1") (pin "1") (pinfunction "1_1") (pintype "passive"))
      (node (ref "JP1") (pin "3") (pinfunction "3_3") (pintype "passive"))
      (node (ref "JP1") (pin "5") (pinfunction "5_5") (pintype "passive"))
      (node (ref "MP1584_12V") (pin "1") (pinfunction "1_1") (pintype "passive"))
      (node (ref "MP1584_12V") (pin "4") (pinfunction "4_4") (pintype "passive"))
      (node (ref "MP1584_3.3V") (pin "1") (pinfunction "1_1") (pintype "passive"))
      (node (ref "MP1584_3.3V") (pin "4") (pinfunction "4_4") (pintype "passive"))
      (node (ref "MP1584_5V") (pin "1") (pinfunction "1_1") (pintype "passive"))
      (node (ref "MP1584_5V") (pin "4") (pinfunction "4_4") (pintype "passive"))
      (node (ref "NQ1") (pin "3") (pinfunction "S_3") (pintype "passive"))
      (node (ref "NQ2") (pin "3") (pinfunction "S_3") (pintype "passive"))
      (node (ref "P10") (pin "1") (pinfunction "X_1") (pintype "passive"))
      (node (ref "P7") (pin "1") (pinfunction "X_1") (pintype "passive"))
      (node (ref "P8") (pin "1") (pinfunction "X_1") (pintype "passive"))
      (node (ref "P9") (pin "1") (pinfunction "X_1") (pintype "passive"))
      (node (ref "Q2") (pin "2") (pinfunction "E_2") (pintype "passive"))
      (node (ref "Q4") (pin "2") (pinfunction "E_2") (pintype "passive"))
      (node (ref "Q5") (pin "2") (pinfunction "E_2") (pintype "passive"))
      (node (ref "R11") (pin "1") (pinfunction "1_1") (pintype "passive"))
      (node (ref "R14") (pin "1") (pinfunction "1_1") (pintype "passive"))
      (node (ref "R15") (pin "2") (pinfunction "2_2") (pintype "passive"))
      (node (ref "R21") (pin "1") (pinfunction "1_1") (pintype "passive"))
      (node (ref "R3") (pin "1") (pinfunction "1_1") (pintype "passive"))
      (node (ref "R42") (pin "2") (pinfunction "2_2") (pintype "passive"))
      (node (ref "R5") (pin "1") (pinfunction "1_1") (pintype "passive"))
      (node (ref "S2") (pin "1") (pinfunction "1_1") (pintype "passive"))
      (node (ref "U34") (pin "3") (pinfunction "GND_3") (pintype "passive"))
      (node (ref "U34") (pin "FIN") (pinfunction "GND_FIN") (pintype "passive"))
      (node (ref "U4") (pin "5") (pinfunction "GND_5") (pintype "power_in"))
      (node (ref "U6") (pin "4") (pinfunction "V-_4") (pintype "power_in"))
      (node (ref "U6") (pin "5") (pinfunction "IN+_5") (pintype "power_in"))
      (node (ref "U6") (pin "6") (pinfunction "IN-_6") (pintype "power_in"))
    )
    (net (code "21") (name "Net-(D6-A1)") (class "Default")
      (node (ref "D6") (pin "1") (pinfunction "A1_1") (pintype "passive"))
      (node (ref "D6") (pin "3") (pinfunction "A2_3") (pintype "passive"))
      (node (ref "L2") (pin "2") (pinfunction "2_2") (pintype "passive"))
      (node (ref "Q1") (pin "2") (pinfunction "D_2") (pintype "passive"))
    )
    (net (code "22") (name "Net-(D7-A)") (class "Default")
      (node (ref "C17") (pin "2") (pinfunction "2_2") (pintype "passive"))
      (node (ref "D7") (pin "1") (pinfunction "A_1") (pintype "passive"))
      (node (ref "Q4") (pin "1") (pinfunction "B_1") (pintype "passive"))
    )
    (net (code "23") (name "Net-(D7-K)") (class "Default")
      (node (ref "D7") (pin "2") (pinfunction "K_2") (pintype "passive"))
      (node (ref "R29") (pin "1") (pinfunction "1_1") (pintype "passive"))
    )
    (net (code "24") (name "Net-(D8-A)") (class "Default")
      (node (ref "C18") (pin "2") (pinfunction "2_2") (pintype "passive"))
      (node (ref "D8") (pin "1") (pinfunction "A_1") (pintype "passive"))
      (node (ref "Q2") (pin "1") (pinfunction "B_1") (pintype "passive"))
    )
    (net (code "25") (name "Net-(D8-K)") (class "Default")
      (node (ref "D8") (pin "2") (pinfunction "K_2") (pintype "passive"))
      (node (ref "R30") (pin "2") (pinfunction "2_2") (pintype "passive"))
    )
    (net (code "26") (name "Net-(D10-A)") (class "Default")
      (node (ref "D10") (pin "1") (pinfunction "A_1") (pintype "passive"))
      (node (ref "R117") (pin "1") (pinfunction "1_1") (pintype "passive"))
    )
    (net (code "27") (name "Net-(D11-K)") (class "Default")
      (node (ref "D11") (pin "2") (pinfunction "K_2") (pintype "passive"))
      (node (ref "D14") (pin "2") (pinfunction "K_2") (pintype "passive"))
      (node (ref "L2") (pin "1") (pinfunction "1_1") (pintype "passive"))
    )
    (net (code "28") (name "Net-(D12-A)") (class "Default")
      (node (ref "D12") (pin "1") (pinfunction "A_1") (pintype "passive"))
      (node (ref "Q1") (pin "3") (pinfunction "S_3") (pintype "passive"))
      (node (ref "R10") (pin "1") (pinfunction "1_1") (pintype "passive"))
      (node (ref "R13") (pin "1") (pinfunction "1_1") (pintype "passive"))
      (node (ref "R14") (pin "2") (pinfunction "2_2") (pintype "passive"))
    )
    (net (code "29") (name "Net-(D12-K)") (class "Default")
      (node (ref "D12") (pin "2") (pinfunction "K_2") (pintype "passive"))
      (node (ref "Q1") (pin "1") (pinfunction "G_1") (pintype "passive"))
      (node (ref "R13") (pin "2") (pinfunction "2_2") (pintype "passive"))
      (node (ref "R8") (pin "2") (pinfunction "2_2") (pintype "passive"))
    )
    (net (code "30") (name "Net-(DS1-A)") (class "Default")
      (node (ref "DS1") (pin "1") (pinfunction "A_1") (pintype "passive"))
      (node (ref "R1") (pin "1") (pinfunction "1_1") (pintype "passive"))
    )
    (net (code "31") (name "Net-(DS2-A)") (class "Default")
      (node (ref "DS2") (pin "1") (pinfunction "A_1") (pintype "passive"))
      (node (ref "R17") (pin "1") (pinfunction "1_1") (pintype "passive"))
    )
    (net (code "32") (name "Net-(DS3-A)") (class "Default")
      (node (ref "DS3") (pin "1") (pinfunction "A_1") (pintype "passive"))
      (node (ref "R36") (pin "1") (pinfunction "1_1") (pintype "passive"))
    )
    (net (code "33") (name "Net-(F5-Pad2)") (class "Default")
      (node (ref "F5") (pin "2") (pinfunction "2_2") (pintype "passive"))
      (node (ref "MP1584_5V") (pin "3") (pinfunction "3_3") (pintype "passive"))
    )
    (net (code "34") (name "Net-(F12-Pad2)") (class "Default")
      (node (ref "F12") (pin "2") (pinfunction "2_2") (pintype "passive"))
      (node (ref "MP1584_12V") (pin "3") (pinfunction "3_3") (pintype "passive"))
    )
    (net (code "35") (name "Net-(F33-Pad2)") (class "Default")
      (node (ref "F33") (pin "2") (pinfunction "2_2") (pintype "passive"))
      (node (ref "MP1584_3.3V") (pin "3") (pinfunction "3_3") (pintype "passive"))
    )
    (net (code "36") (name "Net-(NQ1-G)") (class "Default")
      (node (ref "NQ1") (pin "1") (pinfunction "G_1") (pintype "passive"))
      (node (ref "R2") (pin "2") (pinfunction "2_2") (pintype "passive"))
      (node (ref "R3") (pin "2") (pinfunction "2_2") (pintype "passive"))
    )
    (net (code "37") (name "Net-(NQ2-G)") (class "Default")
      (node (ref "NQ2") (pin "1") (pinfunction "G_1") (pintype "passive"))
      (node (ref "R4") (pin "2") (pinfunction "2_2") (pintype "passive"))
      (node (ref "R5") (pin "2") (pinfunction "2_2") (pintype "passive"))
    )
    (net (code "38") (name "Net-(Q5-B)") (class "Default")
      (node (ref "Q5") (pin "1") (pinfunction "B_1") (pintype "passive"))
      (node (ref "R42") (pin "1") (pinfunction "1_1") (pintype "passive"))
      (node (ref "S2") (pin "2") (pinfunction "2_2") (pintype "passive"))
    )
    (net (code "39") (name "Net-(R41-Pad1)") (class "Default")
      (node (ref "R41") (pin "1") (pinfunction "1_1") (pintype "passive"))
      (node (ref "S2") (pin "3") (pinfunction "3_3") (pintype "passive"))
    )
    (net (code "40") (name "Net-(U4-RT{slash}CT)") (class "Default")
      (node (ref "C11") (pin "1") (pinfunction "1_1") (pintype "passive"))
      (node (ref "R18") (pin "1") (pinfunction "1_1") (pintype "passive"))
      (node (ref "U4") (pin "4") (pinfunction "RT/CT_4") (pintype "passive"))
    )
    (net (code "41") (name "Net-(U6A-IN+)") (class "Default")
      (node (ref "R6") (pin "1") (pinfunction "1_1") (pintype "passive"))
      (node (ref "U6") (pin "3") (pinfunction "IN+_3") (pintype "power_in"))
    )
    (net (code "42") (name "Net-(U6A-IN-)") (class "Default")
      (node (ref "R15") (pin "1") (pinfunction "1_1") (pintype "passive"))
      (node (ref "R9") (pin "1") (pinfunction "1_1") (pintype "passive"))
      (node (ref "U6") (pin "2") (pinfunction "IN-_2") (pintype "power_in"))
    )
    (net (code "43") (name "Net-(U6A-OUT)") (class "Default")
      (node (ref "R16") (pin "1") (pinfunction "1_1") (pintype "passive"))
      (node (ref "R17") (pin "2") (pinfunction "2_2") (pintype "passive"))
      (node (ref "U6") (pin "1") (pinfunction "OUT_1") (pintype "power_in"))
    )
    (net (code "44") (name "Net-(U34-OUT)") (class "Default")
      (node (ref "F34") (pin "1") (pinfunction "1_1") (pintype "passive"))
      (node (ref "U34") (pin "4") (pinfunction "OUT_4") (pintype "passive"))
    )
    (net (code "45") (name "unconnected-(P7-Y-Pad2)") (class "Default")
      (node (ref "P7") (pin "2") (pinfunction "Y_2") (pintype "passive"))
    )
    (net (code "46") (name "unconnected-(P8-Y-Pad2)") (class "Default")
      (node (ref "P8") (pin "2") (pinfunction "Y_2") (pintype "passive"))
    )
    (net (code "47") (name "unconnected-(P9-Y-Pad2)") (class "Default")
      (node (ref "P9") (pin "2") (pinfunction "Y_2") (pintype "passive"))
    )
    (net (code "48") (name "unconnected-(P10-Y-Pad2)") (class "Default")
      (node (ref "P10") (pin "2") (pinfunction "Y_2") (pintype "passive"))
    )
    (net (code "49") (name "unconnected-(U6B-OUT-Pad7)") (class "Default")
      (node (ref "U6") (pin "7") (pinfunction "OUT_7") (pintype "power_in+no_connect"))
    )
    (net (code "50") (name "unconnected-(U6B-V+-Pad8)") (class "Default")
      (node (ref "U6") (pin "8") (pinfunction "V+_8") (pintype "power_in+no_connect"))
    )
    (net (code "51") (name "unconnected-(U6B-V--Pad4)") (class "Default")
      (node (ref "U6") (pin "4") (pinfunction "V-_4") (pintype "power_in+no_connect"))
    )
    (net (code "52") (name "unconnected-(U34-NC-Pad5)") (class "Default")
      (node (ref "U34") (pin "5") (pinfunction "NC_5") (pintype "passive+no_connect"))
    )
  )
)
